# LTC4425_breakout.net
KiCad netlist of a schematic drawn in EAGLE
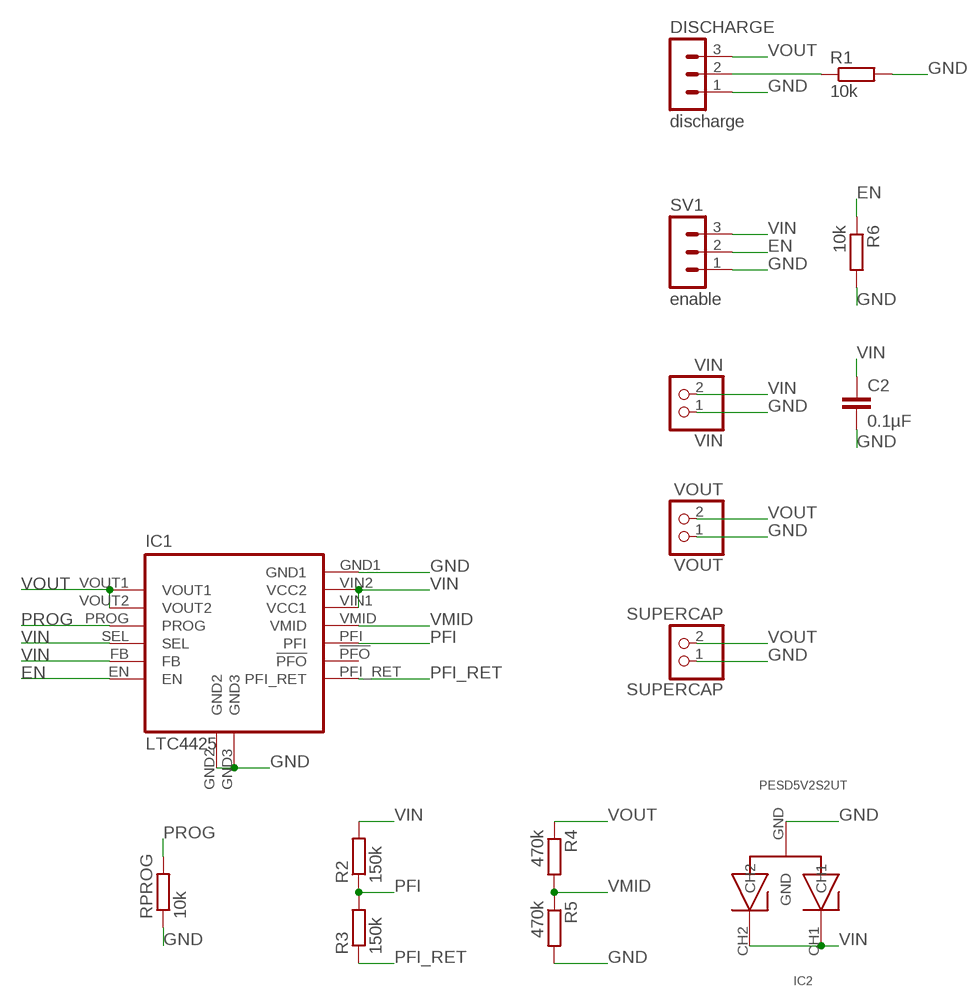
[diagram p0: schematic, sheet 1]

(export (version "E")
  (design (tool "Eeschema 10.0.6"))
  (components
    (comp (ref "C2")
      (value "0.1µF")
      (footprint "eagle-import:C0805")
      (libsource (lib "eagle-import") (part "C-EUC0805"))
    )
    (comp (ref "DISCHARGE")
      (value "discharge")
      (footprint "eagle-import:MA03-1")
      (libsource (lib "eagle-import") (part "MA03-1"))
    )
    (comp (ref "IC1")
      (value "LTC4425")
      (footprint "eagle-import:MSOP")
      (libsource (lib "eagle-import") (part "LTC4425"))
    )
    (comp (ref "IC2")
      (value "PESD5V2S2UT")
      (footprint "eagle-import:SOT-23")
      (libsource (lib "eagle-import") (part "PESDXS2UT"))
    )
    (comp (ref "R1")
      (value "10k")
      (footprint "eagle-import:R1206")
      (libsource (lib "eagle-import") (part "R-EU_R1206"))
    )
    (comp (ref "R2")
      (value "150k")
      (footprint "eagle-import:R0805")
      (libsource (lib "eagle-import") (part "R-EU_R0805"))
    )
    (comp (ref "R3")
      (value "150k")
      (footprint "eagle-import:R0805")
      (libsource (lib "eagle-import") (part "R-EU_R0805"))
    )
    (comp (ref "R4")
      (value "470k")
      (footprint "eagle-import:R0805")
      (libsource (lib "eagle-import") (part "R-EU_R0805"))
    )
    (comp (ref "R5")
      (value "470k")
      (footprint "eagle-import:R0805")
      (libsource (lib "eagle-import") (part "R-EU_R0805"))
    )
    (comp (ref "R6")
      (value "10k")
      (footprint "eagle-import:R0805")
      (libsource (lib "eagle-import") (part "R-EU_R0805"))
    )
    (comp (ref "RPROG")
      (value "10k")
      (footprint "eagle-import:R1206")
      (libsource (lib "eagle-import") (part "R-EU_R1206"))
    )
    (comp (ref "SUPERCAP")
      (value "SUPERCAP")
      (footprint "eagle-import:1X02")
      (libsource (lib "eagle-import") (part "PINHD-1X2"))
    )
    (comp (ref "SV1")
      (value "enable")
      (footprint "eagle-import:MA03-1")
      (libsource (lib "eagle-import") (part "MA03-1"))
    )
    (comp (ref "VIN")
      (value "VIN")
      (footprint "eagle-import:1X02")
      (libsource (lib "eagle-import") (part "PINHD-1X2"))
    )
    (comp (ref "VOUT")
      (value "VOUT")
      (footprint "eagle-import:1X02")
      (libsource (lib "eagle-import") (part "PINHD-1X2"))
    )
  )
  (nets
    (net (code "1") (name "/EN") (class "Default")
      (node (ref "IC1") (pin "EN") (pinfunction "EN_EN") (pintype "bidirectional"))
      (node (ref "R6") (pin "1") (pinfunction "1_1") (pintype "passive"))
      (node (ref "SV1") (pin "2") (pinfunction "2_2") (pintype "passive"))
    )
    (net (code "2") (name "/GND") (class "Default")
      (node (ref "C2") (pin "2") (pinfunction "2_2") (pintype "passive"))
      (node (ref "DISCHARGE") (pin "1") (pinfunction "1_1") (pintype "passive"))
      (node (ref "IC1") (pin "GND1") (pinfunction "GND1_GND1") (pintype "power_in"))
      (node (ref "IC1") (pin "GND2") (pinfunction "GND2_GND2") (pintype "power_in"))
      (node (ref "IC1") (pin "GND3") (pinfunction "GND3_GND3") (pintype "power_in"))
      (node (ref "IC2") (pin "GND") (pinfunction "GND_GND") (pintype "bidirectional"))
      (node (ref "R1") (pin "2") (pinfunction "2_2") (pintype "passive"))
      (node (ref "R5") (pin "2") (pinfunction "2_2") (pintype "passive"))
      (node (ref "R6") (pin "2") (pinfunction "2_2") (pintype "passive"))
      (node (ref "RPROG") (pin "1") (pinfunction "1_1") (pintype "passive"))
      (node (ref "SUPERCAP") (pin "1") (pinfunction "1_1") (pintype "passive"))
      (node (ref "SV1") (pin "1") (pinfunction "1_1") (pintype "passive"))
      (node (ref "VIN") (pin "1") (pinfunction "1_1") (pintype "passive"))
      (node (ref "VOUT") (pin "1") (pinfunction "1_1") (pintype "passive"))
    )
    (net (code "3") (name "/PFI") (class "Default")
      (node (ref "IC1") (pin "PFI") (pinfunction "PFI_PFI") (pintype "output"))
      (node (ref "R2") (pin "1") (pinfunction "1_1") (pintype "passive"))
      (node (ref "R3") (pin "2") (pinfunction "2_2") (pintype "passive"))
    )
    (net (code "4") (name "/PFI_RET") (class "Default")
      (node (ref "IC1") (pin "PFI_RET") (pinfunction "PFI_RET_PFI_RET") (pintype "power_in"))
      (node (ref "R3") (pin "1") (pinfunction "1_1") (pintype "passive"))
    )
    (net (code "5") (name "/PROG") (class "Default")
      (node (ref "IC1") (pin "PROG") (pinfunction "PROG_PROG") (pintype "bidirectional"))
      (node (ref "RPROG") (pin "2") (pinfunction "2_2") (pintype "passive"))
    )
    (net (code "6") (name "/VIN") (class "Default")
      (node (ref "C2") (pin "1") (pinfunction "1_1") (pintype "passive"))
      (node (ref "IC1") (pin "FB") (pinfunction "FB_FB") (pintype "input"))
      (node (ref "IC1") (pin "SEL") (pinfunction "SEL_SEL") (pintype "input"))
      (node (ref "IC1") (pin "VIN1") (pinfunction "VCC1_VIN1") (pintype "bidirectional"))
      (node (ref "IC1") (pin "VIN2") (pinfunction "VCC2_VIN2") (pintype "bidirectional"))
      (node (ref "IC2") (pin "CH1") (pinfunction "CH1_CH1") (pintype "bidirectional"))
      (node (ref "IC2") (pin "CH2") (pinfunction "CH2_CH2") (pintype "bidirectional"))
      (node (ref "R2") (pin "2") (pinfunction "2_2") (pintype "passive"))
      (node (ref "SV1") (pin "3") (pinfunction "3_3") (pintype "passive"))
      (node (ref "VIN") (pin "2") (pinfunction "2_2") (pintype "passive"))
    )
    (net (code "7") (name "/VMID") (class "Default")
      (node (ref "IC1") (pin "VMID") (pinfunction "VMID_VMID") (pintype "output"))
      (node (ref "R4") (pin "2") (pinfunction "2_2") (pintype "passive"))
      (node (ref "R5") (pin "1") (pinfunction "1_1") (pintype "passive"))
    )
    (net (code "8") (name "/VOUT") (class "Default")
      (node (ref "DISCHARGE") (pin "3") (pinfunction "3_3") (pintype "passive"))
      (node (ref "IC1") (pin "VOUT1") (pinfunction "VOUT1_VOUT1") (pintype "bidirectional"))
      (node (ref "IC1") (pin "VOUT2") (pinfunction "VOUT2_VOUT2") (pintype "bidirectional"))
      (node (ref "R4") (pin "1") (pinfunction "1_1") (pintype "passive"))
      (node (ref "SUPERCAP") (pin "2") (pinfunction "2_2") (pintype "passive"))
      (node (ref "VOUT") (pin "2") (pinfunction "2_2") (pintype "passive"))
    )
    (net (code "9") (name "Net-(DISCHARGE-Pad2)") (class "Default")
      (node (ref "DISCHARGE") (pin "2") (pinfunction "2_2") (pintype "passive"))
      (node (ref "R1") (pin "1") (pinfunction "1_1") (pintype "passive"))
    )
    (net (code "10") (name "unconnected-(IC1-~{PFO}-Pad!PFO!)") (class "Default")
      (node (ref "IC1") (pin "!PFO!") (pinfunction "~{PFO}_!PFO!") (pintype "bidirectional"))
    )
  )
)
